# TerminalBlock.net
KiCad netlist of a schematic drawn in EAGLE
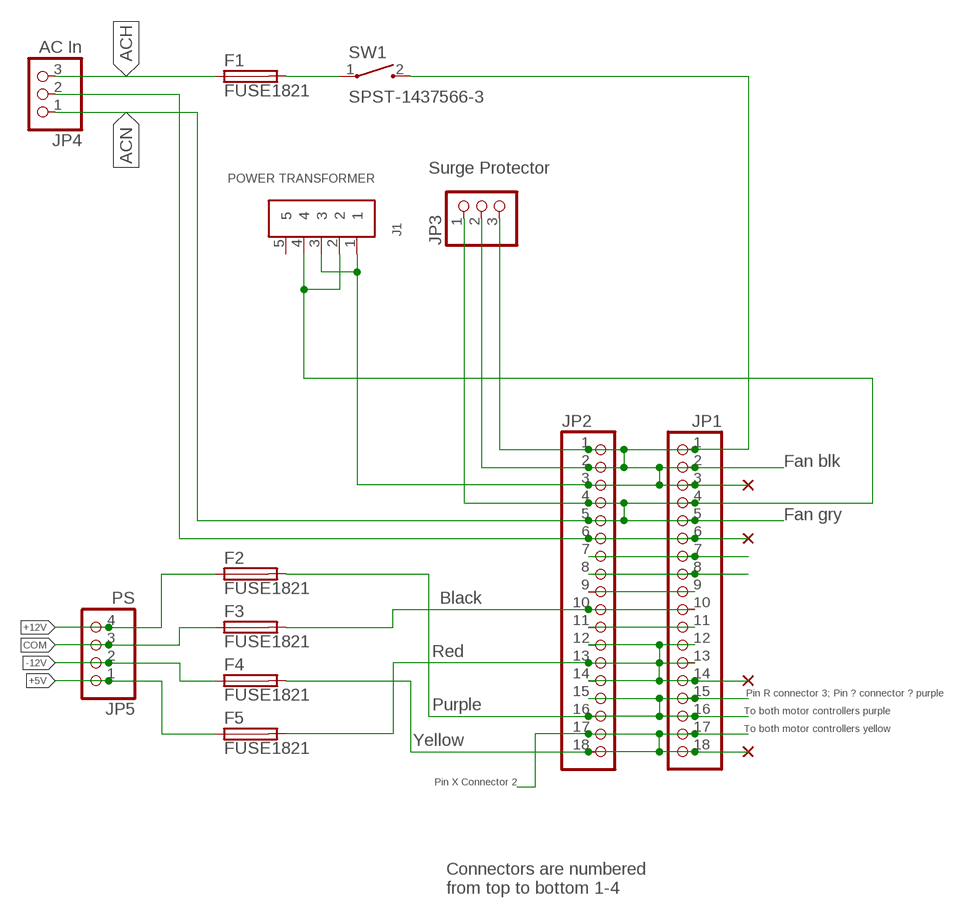
[diagram p0: schematic, sheet 1]

(export (version "E")
  (design (tool "Eeschema 10.0.6"))
  (components
    (comp (ref "F1")
      (value "FUSE1821")
      (footprint "eagle-import:FUSE_HOLDER_MENTOR-1821")
      (libsource (lib "eagle-import") (part "FUSE1821"))
    )
    (comp (ref "F2")
      (value "FUSE1821")
      (footprint "eagle-import:FUSE_HOLDER_MENTOR-1821")
      (libsource (lib "eagle-import") (part "FUSE1821"))
    )
    (comp (ref "F3")
      (value "FUSE1821")
      (footprint "eagle-import:FUSE_HOLDER_MENTOR-1821")
      (libsource (lib "eagle-import") (part "FUSE1821"))
    )
    (comp (ref "F4")
      (value "FUSE1821")
      (footprint "eagle-import:FUSE_HOLDER_MENTOR-1821")
      (libsource (lib "eagle-import") (part "FUSE1821"))
    )
    (comp (ref "F5")
      (value "FUSE1821")
      (footprint "eagle-import:FUSE_HOLDER_MENTOR-1821")
      (libsource (lib "eagle-import") (part "FUSE1821"))
    )
    (comp (ref "J1")
      (value "POWER TRANSFORMER")
      (footprint "eagle-import:1X05-ESQ-105-33-T-S")
      (libsource (lib "eagle-import") (part "PINHD-1X5-ESQ-105-33-T-S"))
    )
    (comp (ref "JP1")
      (value "PINHD-1X18-BIG")
      (footprint "eagle-import:1X18-BIG")
      (libsource (lib "eagle-import") (part "PINHD-1X18-BIG"))
    )
    (comp (ref "JP2")
      (value "PINHD-1X18-BIG")
      (footprint "eagle-import:1X18-BIG")
      (libsource (lib "eagle-import") (part "PINHD-1X18-BIG"))
    )
    (comp (ref "JP3")
      (value "Surge Protector")
      (footprint "eagle-import:1X03")
      (libsource (lib "eagle-import") (part "PINHD-1X3"))
    )
    (comp (ref "JP4")
      (value "AC In")
      (footprint "eagle-import:1X03")
      (libsource (lib "eagle-import") (part "PINHD-1X3"))
    )
    (comp (ref "JP5")
      (value "PS")
      (footprint "eagle-import:1X04")
      (libsource (lib "eagle-import") (part "PINHD-1X4"))
    )
    (comp (ref "SW1")
      (value "SPST-1437566-3")
      (footprint "eagle-import:SW_1437566-3")
      (fields (field (name "MANUFACTURER") "TE CONNECTIVITY"))
      (libsource (lib "eagle-import") (part "SPST-1437566-3"))
    )
  )
  (nets
    (net (code "1") (name "+5V") (class "Default")
      (node (ref "F5") (pin "A") (pinfunction "1_A") (pintype "passive"))
      (node (ref "JP5") (pin "1") (pinfunction "1_1") (pintype "passive"))
    )
    (net (code "2") (name "+12V") (class "Default")
      (node (ref "F2") (pin "A") (pinfunction "1_A") (pintype "passive"))
      (node (ref "JP5") (pin "4") (pinfunction "4_4") (pintype "passive"))
    )
    (net (code "3") (name "-12V") (class "Default")
      (node (ref "F4") (pin "A") (pinfunction "1_A") (pintype "passive"))
      (node (ref "JP5") (pin "2") (pinfunction "2_2") (pintype "passive"))
    )
    (net (code "4") (name "ACH") (class "Default")
      (node (ref "F1") (pin "A") (pinfunction "1_A") (pintype "passive"))
      (node (ref "J1") (pin "1") (pinfunction "1_1") (pintype "bidirectional"))
      (node (ref "J1") (pin "3") (pinfunction "3_3") (pintype "bidirectional"))
      (node (ref "JP1") (pin "1") (pinfunction "1_1") (pintype "passive"))
      (node (ref "JP1") (pin "2") (pinfunction "2_2") (pintype "passive"))
      (node (ref "JP1") (pin "3") (pinfunction "3_3") (pintype "passive"))
      (node (ref "JP2") (pin "1") (pinfunction "1_1") (pintype "passive"))
      (node (ref "JP2") (pin "2") (pinfunction "2_2") (pintype "passive"))
      (node (ref "JP2") (pin "3") (pinfunction "3_3") (pintype "passive"))
      (node (ref "JP3") (pin "2") (pinfunction "2_2") (pintype "passive"))
      (node (ref "JP3") (pin "3") (pinfunction "3_3") (pintype "passive"))
      (node (ref "JP4") (pin "3") (pinfunction "3_3") (pintype "passive"))
      (node (ref "SW1") (pin "2") (pinfunction "2_2") (pintype "passive"))
    )
    (net (code "5") (name "ACN") (class "Default")
      (node (ref "J1") (pin "2") (pinfunction "2_2") (pintype "bidirectional"))
      (node (ref "J1") (pin "4") (pinfunction "4_4") (pintype "bidirectional"))
      (node (ref "JP1") (pin "4") (pinfunction "4_4") (pintype "passive"))
      (node (ref "JP1") (pin "5") (pinfunction "5_5") (pintype "passive"))
      (node (ref "JP2") (pin "4") (pinfunction "4_4") (pintype "passive"))
      (node (ref "JP2") (pin "5") (pinfunction "5_5") (pintype "passive"))
      (node (ref "JP3") (pin "1") (pinfunction "1_1") (pintype "passive"))
      (node (ref "JP4") (pin "1") (pinfunction "1_1") (pintype "passive"))
    )
    (net (code "6") (name "COM") (class "Default")
      (node (ref "F3") (pin "A") (pinfunction "1_A") (pintype "passive"))
      (node (ref "JP5") (pin "3") (pinfunction "3_3") (pintype "passive"))
    )
    (net (code "7") (name "Net-(F1-2)") (class "Default")
      (node (ref "F1") (pin "B") (pinfunction "2_B") (pintype "passive"))
      (node (ref "SW1") (pin "1") (pinfunction "1_1") (pintype "passive"))
    )
    (net (code "8") (name "Net-(F2-2)") (class "Default")
      (node (ref "F2") (pin "B") (pinfunction "2_B") (pintype "passive"))
      (node (ref "JP1") (pin "15") (pinfunction "15_15") (pintype "passive"))
      (node (ref "JP1") (pin "16") (pinfunction "16_16") (pintype "passive"))
      (node (ref "JP2") (pin "15") (pinfunction "15_15") (pintype "passive"))
      (node (ref "JP2") (pin "16") (pinfunction "16_16") (pintype "passive"))
    )
    (net (code "9") (name "Net-(F3-2)") (class "Default")
      (node (ref "F3") (pin "B") (pinfunction "2_B") (pintype "passive"))
      (node (ref "JP1") (pin "10") (pinfunction "10_10") (pintype "passive"))
      (node (ref "JP2") (pin "10") (pinfunction "10_10") (pintype "passive"))
    )
    (net (code "10") (name "Net-(F4-2)") (class "Default")
      (node (ref "F4") (pin "B") (pinfunction "2_B") (pintype "passive"))
      (node (ref "JP1") (pin "17") (pinfunction "17_17") (pintype "passive"))
      (node (ref "JP1") (pin "18") (pinfunction "18_18") (pintype "passive"))
      (node (ref "JP2") (pin "17") (pinfunction "17_17") (pintype "passive"))
      (node (ref "JP2") (pin "18") (pinfunction "18_18") (pintype "passive"))
    )
    (net (code "11") (name "Net-(F5-2)") (class "Default")
      (node (ref "F5") (pin "B") (pinfunction "2_B") (pintype "passive"))
      (node (ref "JP1") (pin "12") (pinfunction "12_12") (pintype "passive"))
      (node (ref "JP1") (pin "13") (pinfunction "13_13") (pintype "passive"))
      (node (ref "JP1") (pin "14") (pinfunction "14_14") (pintype "passive"))
      (node (ref "JP2") (pin "12") (pinfunction "12_12") (pintype "passive"))
      (node (ref "JP2") (pin "13") (pinfunction "13_13") (pintype "passive"))
      (node (ref "JP2") (pin "14") (pinfunction "14_14") (pintype "passive"))
    )
    (net (code "12") (name "Net-(JP1-Pad6)") (class "Default")
      (node (ref "JP1") (pin "6") (pinfunction "6_6") (pintype "passive"))
      (node (ref "JP2") (pin "6") (pinfunction "6_6") (pintype "passive"))
      (node (ref "JP4") (pin "2") (pinfunction "2_2") (pintype "passive"))
    )
    (net (code "13") (name "Net-(JP1-Pad7)") (class "Default")
      (node (ref "JP1") (pin "7") (pinfunction "7_7") (pintype "passive"))
      (node (ref "JP2") (pin "7") (pinfunction "7_7") (pintype "passive"))
    )
    (net (code "14") (name "Net-(JP1-Pad8)") (class "Default")
      (node (ref "JP1") (pin "8") (pinfunction "8_8") (pintype "passive"))
      (node (ref "JP2") (pin "8") (pinfunction "8_8") (pintype "passive"))
    )
    (net (code "15") (name "Net-(JP1-Pad9)") (class "Default")
      (node (ref "JP1") (pin "9") (pinfunction "9_9") (pintype "passive"))
      (node (ref "JP2") (pin "9") (pinfunction "9_9") (pintype "passive"))
    )
    (net (code "16") (name "Net-(JP1-Pad11)") (class "Default")
      (node (ref "JP1") (pin "11") (pinfunction "11_11") (pintype "passive"))
      (node (ref "JP2") (pin "11") (pinfunction "11_11") (pintype "passive"))
    )
    (net (code "17") (name "unconnected-(J1-Pad5)") (class "Default")
      (node (ref "J1") (pin "5") (pinfunction "5_5") (pintype "bidirectional"))
    )
  )
)
